# FUSE_RVP_OVP14V7.net
KiCad netlist of a schematic drawn in Altium Designer
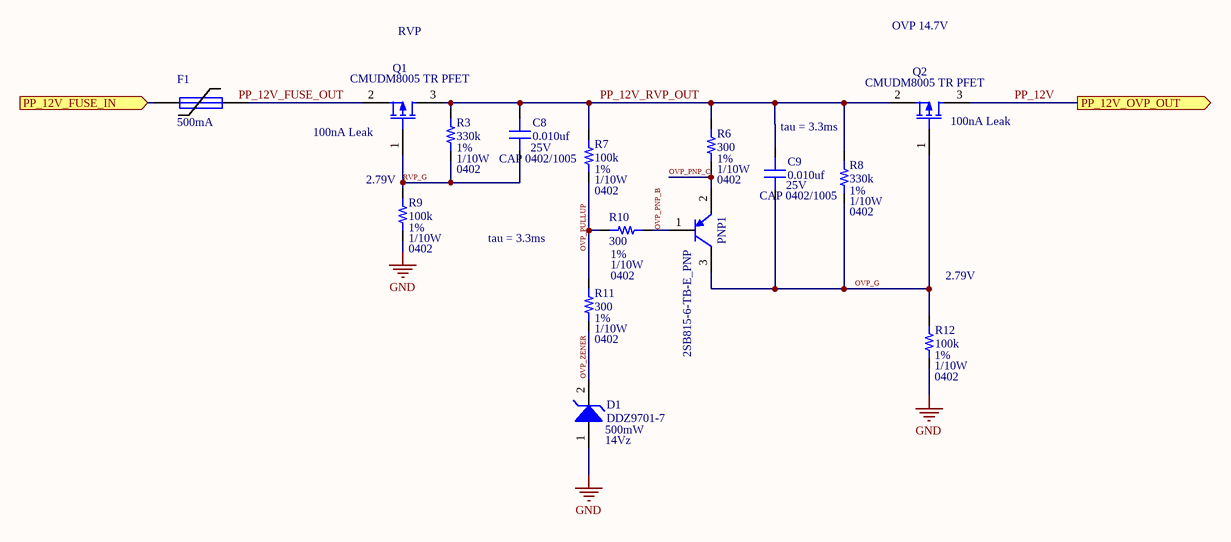
[diagram p0: FUSE_RVP_OVP14V7.SchDoc]

(export (version "E")
  (design (tool "Eeschema 10.0.6"))
  (components
    (comp (ref "C8")
      (value "0.010uf")
      (footprint "CAP 0402/1005")
      (fields
        (field (name "VOLTAGE_RATING") "25V")
        (field (name "PACKAGE") "CAP 0402/1005")
        (field (name "Comment") "Capacitor MLCC 0.010uf 25V CAP 0402/1005")
        (field (name "CREATED_BY") "Nick Mah")
      )
      (libsource (lib "Altium-Lib") (part "Capacitor"))
    )
    (comp (ref "C9")
      (value "0.010uf")
      (footprint "CAP 0402/1005")
      (fields
        (field (name "VOLTAGE_RATING") "25V")
        (field (name "PACKAGE") "CAP 0402/1005")
        (field (name "Comment") "Capacitor MLCC 0.010uf 25V CAP 0402/1005")
        (field (name "CREATED_BY") "Nick Mah")
      )
      (libsource (lib "Altium-Lib") (part "Capacitor"))
    )
    (comp (ref "D1")
      (value "DDZ9701-7")
      (footprint "SOD123F")
      (description "Zener Diode 14V 500mW ±5% Surface Mount SOD-123")
      (fields (field (name "ALTIUM_VALUE") "14Vz") (field (name "POWER") "500mW"))
      (libsource (lib "Altium-Lib") (part "Zener"))
    )
    (comp (ref "F1")
      (value "1A")
      (footprint "PIN-W2/E2.8")
      (description "Fuse")
      (fields
        (field (name "I_HOLD") "500mA")
        (field (name "MFRPARTNO") "1206L050/15YR")
        (field (name "PUBLISHER") "Altium Limited")
        (field (name "CREATED_BY") "Angel")
      )
      (libsource (lib "Altium-Lib") (part "PTC Fuse"))
    )
    (comp (ref "PNP1")
      (value "2SB815-6-TB-E_PNP")
      (footprint "SOT23-3")
      (description "TRANS PNP 15V 0.7A CP")
      (fields
        (field (name "POWER") "Null")
        (field (name "MFRPARTNO") "2SB815-6-TB-E")
        (field (name "CREATED_BY") "None")
        (field (name "UPDATED_BY") "Null")
      )
      (libsource (lib "Altium-Lib") (part "2SB815-6-TB-E_PNP"))
    )
    (comp (ref "Q1")
      (value "CMUDM8005 TR PFET")
      (footprint "CMUDM8005 TR SOT523")
      (description "MOSFET P-CH 20V 650MA SOT523")
      (fields
        (field (name "MFRPARTNO") "CMUDM8005 TR")
        (field (name "CREATED_BY") "Null")
        (field (name "UPDATED_BY") "Null")
      )
      (libsource (lib "Altium-Lib") (part "CMUDM8005 TR PFET"))
    )
    (comp (ref "Q2")
      (value "CMUDM8005 TR PFET")
      (footprint "CMUDM8005 TR SOT523")
      (description "MOSFET P-CH 20V 650MA SOT523")
      (fields
        (field (name "MFRPARTNO") "CMUDM8005 TR")
        (field (name "CREATED_BY") "Null")
        (field (name "UPDATED_BY") "Null")
      )
      (libsource (lib "Altium-Lib") (part "CMUDM8005 TR PFET"))
    )
    (comp (ref "R3")
      (value "330k")
      (footprint "RES 0402/1005")
      (fields
        (field (name "TOLERANCE") "1%")
        (field (name "POWER") "1/10W")
        (field (name "PACKAGE") "0402")
        (field (name "Comment") "Resistor 330k 0402 1/10W 1%")
        (field (name "CREATED_BY") "Nick Mah")
      )
      (libsource (lib "Altium-Lib") (part "Resistor"))
    )
    (comp (ref "R6")
      (value "300")
      (footprint "RES 0402/1005")
      (fields
        (field (name "TOLERANCE") "1%")
        (field (name "POWER") "1/10W")
        (field (name "PACKAGE") "0402")
        (field (name "Comment") "Resistor 300 0402 1/10W 1%")
        (field (name "CREATED_BY") "Nick Mah")
      )
      (libsource (lib "Altium-Lib") (part "Resistor"))
    )
    (comp (ref "R7")
      (value "100k")
      (footprint "RES 0402/1005")
      (fields
        (field (name "TOLERANCE") "1%")
        (field (name "POWER") "1/10W")
        (field (name "PACKAGE") "0402")
        (field (name "Comment") "Resistor 100k 0402 1/10W 1%")
        (field (name "CREATED_BY") "Nick Mah")
      )
      (libsource (lib "Altium-Lib") (part "Resistor"))
    )
    (comp (ref "R8")
      (value "330k")
      (footprint "RES 0402/1005")
      (fields
        (field (name "TOLERANCE") "1%")
        (field (name "POWER") "1/10W")
        (field (name "PACKAGE") "0402")
        (field (name "Comment") "Resistor 330k 0402 1/10W 1%")
        (field (name "CREATED_BY") "Nick Mah")
      )
      (libsource (lib "Altium-Lib") (part "Resistor"))
    )
    (comp (ref "R9")
      (value "100k")
      (footprint "RES 0402/1005")
      (fields
        (field (name "TOLERANCE") "1%")
        (field (name "POWER") "1/10W")
        (field (name "PACKAGE") "0402")
        (field (name "Comment") "Resistor 100k 0402 1/10W 1%")
        (field (name "CREATED_BY") "Nick Mah")
      )
      (libsource (lib "Altium-Lib") (part "Resistor"))
    )
    (comp (ref "R10")
      (value "300")
      (footprint "RES 0402/1005")
      (fields
        (field (name "TOLERANCE") "1%")
        (field (name "POWER") "1/10W")
        (field (name "PACKAGE") "0402")
        (field (name "Comment") "Resistor 300 0402 1/10W 1%")
        (field (name "CREATED_BY") "Nick Mah")
      )
      (libsource (lib "Altium-Lib") (part "Resistor"))
    )
    (comp (ref "R11")
      (value "300")
      (footprint "RES 0402/1005")
      (fields
        (field (name "TOLERANCE") "1%")
        (field (name "POWER") "1/10W")
        (field (name "PACKAGE") "0402")
        (field (name "Comment") "Resistor 300 0402 1/10W 1%")
        (field (name "CREATED_BY") "Nick Mah")
      )
      (libsource (lib "Altium-Lib") (part "Resistor"))
    )
    (comp (ref "R12")
      (value "100k")
      (footprint "RES 0402/1005")
      (fields
        (field (name "TOLERANCE") "1%")
        (field (name "POWER") "1/10W")
        (field (name "PACKAGE") "0402")
        (field (name "Comment") "Resistor 100k 0402 1/10W 1%")
        (field (name "CREATED_BY") "Nick Mah")
      )
      (libsource (lib "Altium-Lib") (part "Resistor"))
    )
  )
  (nets
    (net (code "1") (name "/OVP_G") (class "Default")
      (node (ref "C9") (pin "1") (pinfunction "1_1") (pintype "passive"))
      (node (ref "PNP1") (pin "3") (pinfunction "C_3") (pintype "passive"))
      (node (ref "Q2") (pin "1") (pinfunction "G_1") (pintype "passive"))
      (node (ref "R12") (pin "2") (pinfunction "2_2") (pintype "passive"))
      (node (ref "R8") (pin "1") (pinfunction "1_1") (pintype "passive"))
    )
    (net (code "2") (name "/OVP_PNP_B") (class "Default")
      (node (ref "PNP1") (pin "1") (pinfunction "B_1") (pintype "passive"))
      (node (ref "R10") (pin "1") (pinfunction "1_1") (pintype "passive"))
    )
    (net (code "3") (name "/OVP_PNP_C") (class "Default")
      (node (ref "PNP1") (pin "2") (pinfunction "E_2") (pintype "passive"))
      (node (ref "R6") (pin "1") (pinfunction "1_1") (pintype "passive"))
    )
    (net (code "4") (name "/OVP_PULLUP") (class "Default")
      (node (ref "R10") (pin "2") (pinfunction "2_2") (pintype "passive"))
      (node (ref "R11") (pin "2") (pinfunction "2_2") (pintype "passive"))
      (node (ref "R7") (pin "1") (pinfunction "1_1") (pintype "passive"))
    )
    (net (code "5") (name "/OVP_ZENER") (class "Default")
      (node (ref "D1") (pin "2") (pinfunction "K_2") (pintype "passive"))
      (node (ref "R11") (pin "1") (pinfunction "1_1") (pintype "passive"))
    )
    (net (code "6") (name "/PP_12V") (class "Default")
      (node (ref "Q2") (pin "3") (pinfunction "D_3") (pintype "passive"))
    )
    (net (code "7") (name "/PP_12V_FUSE_IN") (class "Default")
      (node (ref "F1") (pin "1") (pinfunction "1_1") (pintype "passive"))
    )
    (net (code "9") (name "/PP_12V_RVP_OUT") (class "Default")
      (node (ref "C8") (pin "2") (pinfunction "2_2") (pintype "passive"))
      (node (ref "C9") (pin "2") (pinfunction "2_2") (pintype "passive"))
      (node (ref "Q1") (pin "3") (pinfunction "D_3") (pintype "passive"))
      (node (ref "Q2") (pin "2") (pinfunction "S_2") (pintype "passive"))
      (node (ref "R3") (pin "2") (pinfunction "2_2") (pintype "passive"))
      (node (ref "R6") (pin "2") (pinfunction "2_2") (pintype "passive"))
      (node (ref "R7") (pin "2") (pinfunction "2_2") (pintype "passive"))
      (node (ref "R8") (pin "2") (pinfunction "2_2") (pintype "passive"))
    )
    (net (code "10") (name "/RVP_G") (class "Default")
      (node (ref "C8") (pin "1") (pinfunction "1_1") (pintype "passive"))
      (node (ref "Q1") (pin "1") (pinfunction "G_1") (pintype "passive"))
      (node (ref "R3") (pin "1") (pinfunction "1_1") (pintype "passive"))
      (node (ref "R9") (pin "2") (pinfunction "2_2") (pintype "passive"))
    )
    (net (code "11") (name "GND") (class "Default")
      (node (ref "D1") (pin "1") (pinfunction "A_1") (pintype "passive"))
      (node (ref "R12") (pin "1") (pinfunction "1_1") (pintype "passive"))
      (node (ref "R9") (pin "1") (pinfunction "1_1") (pintype "passive"))
    )
    (net (code "12") (name "Net-(Q1-S)") (class "Default")
      (node (ref "F1") (pin "2") (pinfunction "2_2") (pintype "passive"))
      (node (ref "Q1") (pin "2") (pinfunction "S_2") (pintype "passive"))
    )
  )
)
